# BNC_1_1.net
KiCad netlist of a schematic drawn in EAGLE
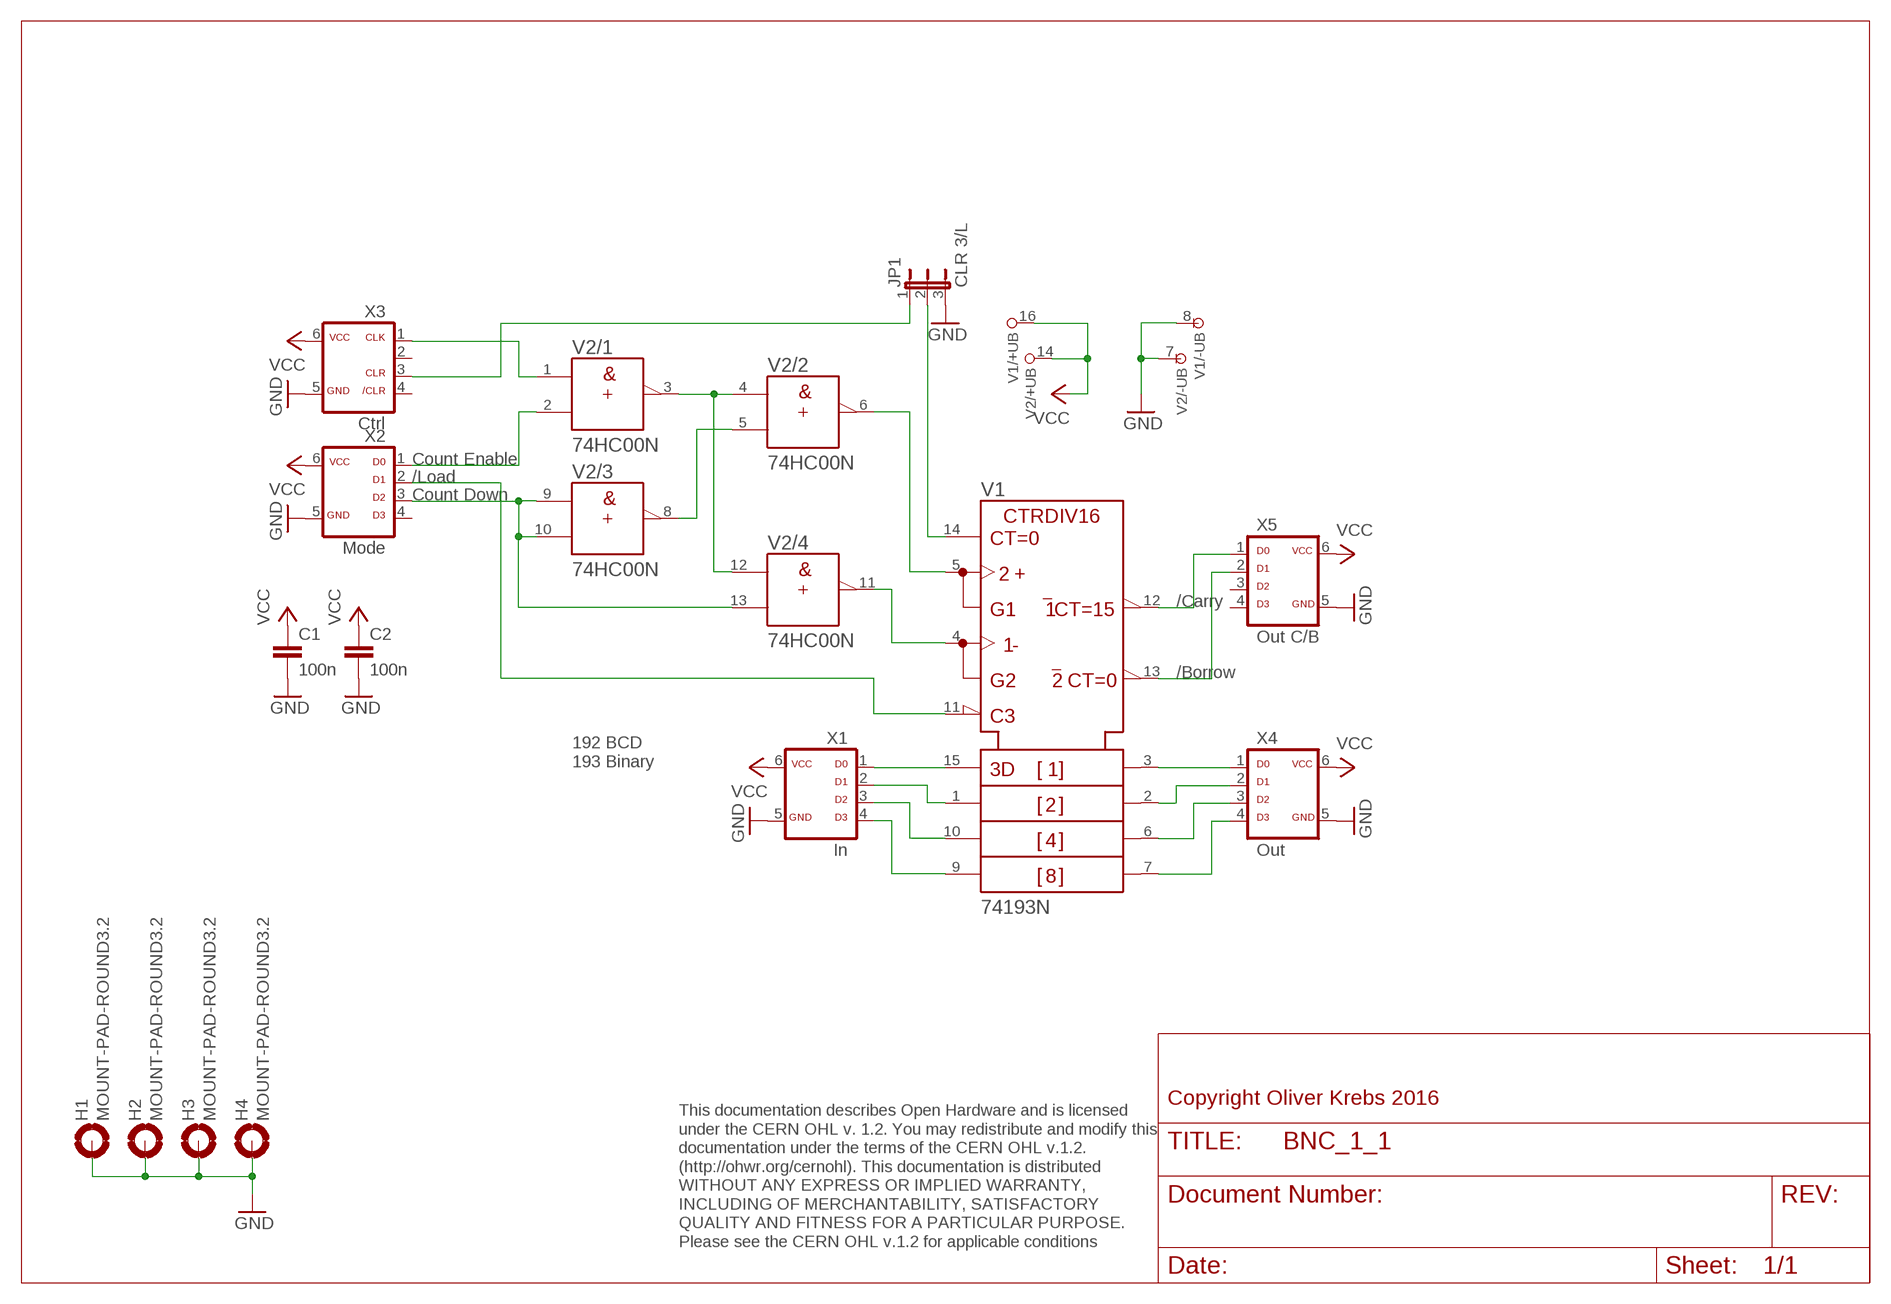
[diagram p0: schematic, sheet 1]

(export (version "E")
  (design (tool "Eeschema 10.0.6"))
  (components
    (comp (ref "C1")
      (value "100n")
      (footprint "eagle-import:C050-025X075")
      (libsource (lib "eagle-import") (part "C-EU050-025X075"))
    )
    (comp (ref "C2")
      (value "100n")
      (footprint "eagle-import:C050-025X075")
      (libsource (lib "eagle-import") (part "C-EU050-025X075"))
    )
    (comp (ref "H1")
      (value "MOUNT-PAD-ROUND3.2")
      (footprint "eagle-import:3,2-PAD")
      (libsource (lib "eagle-import") (part "MOUNT-PAD-ROUND3.2"))
    )
    (comp (ref "H2")
      (value "MOUNT-PAD-ROUND3.2")
      (footprint "eagle-import:3,2-PAD")
      (libsource (lib "eagle-import") (part "MOUNT-PAD-ROUND3.2"))
    )
    (comp (ref "H3")
      (value "MOUNT-PAD-ROUND3.2")
      (footprint "eagle-import:3,2-PAD")
      (libsource (lib "eagle-import") (part "MOUNT-PAD-ROUND3.2"))
    )
    (comp (ref "H4")
      (value "MOUNT-PAD-ROUND3.2")
      (footprint "eagle-import:3,2-PAD")
      (libsource (lib "eagle-import") (part "MOUNT-PAD-ROUND3.2"))
    )
    (comp (ref "JP1")
      (value "CLR 3/L")
      (footprint "eagle-import:JP2")
      (libsource (lib "eagle-import") (part "JP2E"))
    )
    (comp (ref "V1")
      (value "74193N")
      (footprint "eagle-import:DIL16")
      (libsource (lib "eagle-import") (part "74193N"))
    )
    (comp (ref "V2")
      (value "74HC00N")
      (footprint "eagle-import:DIL14")
      (libsource (lib "eagle-import") (part "7400NHC"))
    )
    (comp (ref "X1")
      (value "In")
      (footprint "eagle-import:ML-6")
      (libsource (lib "eagle-import") (part "ML6D"))
    )
    (comp (ref "X2")
      (value "Mode")
      (footprint "eagle-import:ML-6")
      (libsource (lib "eagle-import") (part "ML6D"))
    )
    (comp (ref "X3")
      (value "Ctrl")
      (footprint "eagle-import:ML-6")
      (libsource (lib "eagle-import") (part "ML6C"))
    )
    (comp (ref "X4")
      (value "Out")
      (footprint "eagle-import:ML-6")
      (libsource (lib "eagle-import") (part "ML6D"))
    )
    (comp (ref "X5")
      (value "Out C/B")
      (footprint "eagle-import:ML-6")
      (libsource (lib "eagle-import") (part "ML6D"))
    )
  )
  (nets
    (net (code "1") (name "GND") (class "Default")
      (node (ref "C1") (pin "2") (pinfunction "2_2") (pintype "passive"))
      (node (ref "C2") (pin "2") (pinfunction "2_2") (pintype "passive"))
      (node (ref "H1") (pin "B3,2") (pinfunction "MOUNT_B3,2") (pintype "passive"))
      (node (ref "H2") (pin "B3,2") (pinfunction "MOUNT_B3,2") (pintype "passive"))
      (node (ref "H3") (pin "B3,2") (pinfunction "MOUNT_B3,2") (pintype "passive"))
      (node (ref "H4") (pin "B3,2") (pinfunction "MOUNT_B3,2") (pintype "passive"))
      (node (ref "JP1") (pin "3") (pinfunction "3_3") (pintype "passive"))
      (node (ref "V1") (pin "8") (pinfunction "-UB_8") (pintype "power_in"))
      (node (ref "V2") (pin "7") (pinfunction "-UB_7") (pintype "power_in"))
      (node (ref "X1") (pin "5") (pinfunction "5_5") (pintype "passive"))
      (node (ref "X2") (pin "5") (pinfunction "5_5") (pintype "passive"))
      (node (ref "X3") (pin "5") (pinfunction "5_5") (pintype "passive"))
      (node (ref "X4") (pin "5") (pinfunction "5_5") (pintype "passive"))
      (node (ref "X5") (pin "5") (pinfunction "5_5") (pintype "passive"))
    )
    (net (code "2") (name "Net-(JP1-Pad1)") (class "Default")
      (node (ref "JP1") (pin "1") (pinfunction "1_1") (pintype "passive"))
      (node (ref "X3") (pin "3") (pinfunction "3_3") (pintype "passive"))
    )
    (net (code "3") (name "Net-(V1C-A)") (class "Default")
      (node (ref "V1") (pin "15") (pinfunction "A_15") (pintype "input"))
      (node (ref "X1") (pin "1") (pinfunction "1_1") (pintype "passive"))
    )
    (net (code "4") (name "Net-(V1C-B)") (class "Default")
      (node (ref "V1") (pin "1") (pinfunction "B_1") (pintype "input"))
      (node (ref "X1") (pin "2") (pinfunction "2_2") (pintype "passive"))
    )
    (net (code "5") (name "Net-(V1C-C)") (class "Default")
      (node (ref "V1") (pin "10") (pinfunction "C_10") (pintype "input"))
      (node (ref "X1") (pin "3") (pinfunction "3_3") (pintype "passive"))
    )
    (net (code "6") (name "Net-(V1C-CLR)") (class "Default")
      (node (ref "JP1") (pin "2") (pinfunction "2_2") (pintype "passive"))
      (node (ref "V1") (pin "14") (pinfunction "CLR_14") (pintype "input"))
    )
    (net (code "7") (name "Net-(V1C-D)") (class "Default")
      (node (ref "V1") (pin "9") (pinfunction "D_9") (pintype "input"))
      (node (ref "X1") (pin "4") (pinfunction "4_4") (pintype "passive"))
    )
    (net (code "8") (name "Net-(V1C-DOWN)") (class "Default")
      (node (ref "V1") (pin "4") (pinfunction "DOWN_4") (pintype "input"))
      (node (ref "V2") (pin "11") (pinfunction "Y_11") (pintype "output"))
    )
    (net (code "9") (name "Net-(V1C-QA)") (class "Default")
      (node (ref "V1") (pin "3") (pinfunction "QA_3") (pintype "output"))
      (node (ref "X4") (pin "1") (pinfunction "1_1") (pintype "passive"))
    )
    (net (code "10") (name "Net-(V1C-QB)") (class "Default")
      (node (ref "V1") (pin "2") (pinfunction "QB_2") (pintype "output"))
      (node (ref "X4") (pin "2") (pinfunction "2_2") (pintype "passive"))
    )
    (net (code "11") (name "Net-(V1C-QC)") (class "Default")
      (node (ref "V1") (pin "6") (pinfunction "QC_6") (pintype "output"))
      (node (ref "X4") (pin "3") (pinfunction "3_3") (pintype "passive"))
    )
    (net (code "12") (name "Net-(V1C-QD)") (class "Default")
      (node (ref "V1") (pin "7") (pinfunction "QD_7") (pintype "output"))
      (node (ref "X4") (pin "4") (pinfunction "4_4") (pintype "passive"))
    )
    (net (code "13") (name "Net-(V1C-UP)") (class "Default")
      (node (ref "V1") (pin "5") (pinfunction "UP_5") (pintype "input"))
      (node (ref "V2") (pin "6") (pinfunction "Y_6") (pintype "output"))
    )
    (net (code "14") (name "Net-(V1C-~{BO})") (class "Default")
      (node (ref "V1") (pin "13") (pinfunction "~{BO}_13") (pintype "output"))
      (node (ref "X5") (pin "2") (pinfunction "2_2") (pintype "passive"))
    )
    (net (code "15") (name "Net-(V1C-~{CO})") (class "Default")
      (node (ref "V1") (pin "12") (pinfunction "~{CO}_12") (pintype "output"))
      (node (ref "X5") (pin "1") (pinfunction "1_1") (pintype "passive"))
    )
    (net (code "16") (name "Net-(V1C-~{LOAD})") (class "Default")
      (node (ref "V1") (pin "11") (pinfunction "~{LOAD}_11") (pintype "input"))
      (node (ref "X2") (pin "2") (pinfunction "2_2") (pintype "passive"))
    )
    (net (code "17") (name "Net-(V2C-A)") (class "Default")
      (node (ref "V2") (pin "1") (pinfunction "A_1") (pintype "input"))
      (node (ref "X3") (pin "1") (pinfunction "1_1") (pintype "passive"))
    )
    (net (code "18") (name "Net-(V2C-B)") (class "Default")
      (node (ref "V2") (pin "2") (pinfunction "B_2") (pintype "input"))
      (node (ref "X2") (pin "1") (pinfunction "1_1") (pintype "passive"))
    )
    (net (code "19") (name "Net-(V2C-Y)") (class "Default")
      (node (ref "V2") (pin "12") (pinfunction "A_12") (pintype "input"))
      (node (ref "V2") (pin "3") (pinfunction "Y_3") (pintype "output"))
      (node (ref "V2") (pin "4") (pinfunction "A_4") (pintype "input"))
    )
    (net (code "20") (name "Net-(V2D-B)") (class "Default")
      (node (ref "V2") (pin "5") (pinfunction "B_5") (pintype "input"))
      (node (ref "V2") (pin "8") (pinfunction "Y_8") (pintype "output"))
    )
    (net (code "21") (name "Net-(V2E-A)") (class "Default")
      (node (ref "V2") (pin "10") (pinfunction "B_10") (pintype "input"))
      (node (ref "V2") (pin "13") (pinfunction "B_13") (pintype "input"))
      (node (ref "V2") (pin "9") (pinfunction "A_9") (pintype "input"))
      (node (ref "X2") (pin "3") (pinfunction "3_3") (pintype "passive"))
    )
    (net (code "22") (name "VCC") (class "Default")
      (node (ref "C1") (pin "1") (pinfunction "1_1") (pintype "passive"))
      (node (ref "C2") (pin "1") (pinfunction "1_1") (pintype "passive"))
      (node (ref "V1") (pin "16") (pinfunction "+UB_16") (pintype "power_in"))
      (node (ref "V2") (pin "14") (pinfunction "+UB_14") (pintype "power_in"))
      (node (ref "X1") (pin "6") (pinfunction "6_6") (pintype "passive"))
      (node (ref "X2") (pin "6") (pinfunction "6_6") (pintype "passive"))
      (node (ref "X3") (pin "6") (pinfunction "6_6") (pintype "passive"))
      (node (ref "X4") (pin "6") (pinfunction "6_6") (pintype "passive"))
      (node (ref "X5") (pin "6") (pinfunction "6_6") (pintype "passive"))
    )
    (net (code "23") (name "unconnected-(X2-Pad4)") (class "Default")
      (node (ref "X2") (pin "4") (pinfunction "4_4") (pintype "passive"))
    )
    (net (code "24") (name "unconnected-(X3-Pad2)") (class "Default")
      (node (ref "X3") (pin "2") (pinfunction "2_2") (pintype "passive"))
    )
    (net (code "25") (name "unconnected-(X3-Pad4)") (class "Default")
      (node (ref "X3") (pin "4") (pinfunction "4_4") (pintype "passive"))
    )
    (net (code "26") (name "unconnected-(X5-Pad3)") (class "Default")
      (node (ref "X5") (pin "3") (pinfunction "3_3") (pintype "passive"))
    )
    (net (code "27") (name "unconnected-(X5-Pad4)") (class "Default")
      (node (ref "X5") (pin "4") (pinfunction "4_4") (pintype "passive"))
    )
  )
)
